# Sheet1.net
KiCad netlist of a schematic drawn in Altium Designer
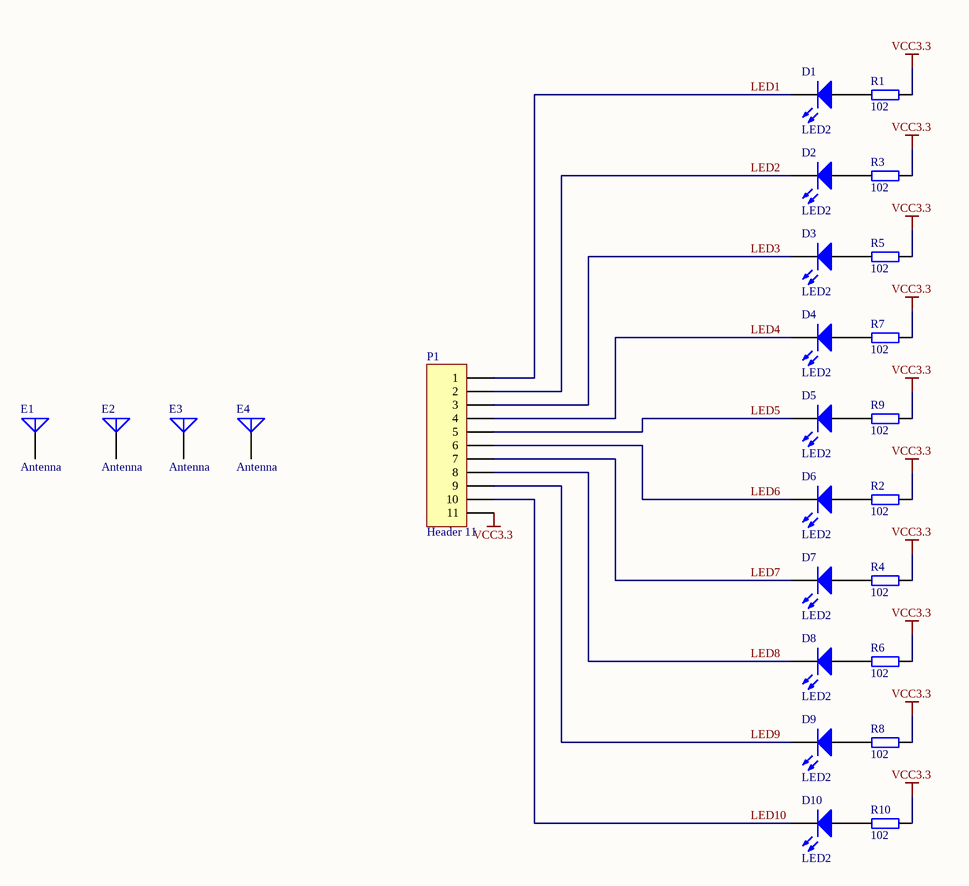
[diagram p0: Sheet1.SchDoc]

(export (version "E")
  (design (tool "Eeschema 10.0.6"))
  (components
    (comp (ref "D1")
      (value "LED2")
      (footprint "LED1")
      (description "Typical RED, GREEN, YELLOW, AMBER GaAs LED")
      (fields (field (name "PUBLISHER") "Altium Limited"))
      (libsource (lib "Miscellaneous Devices") (part "LED2"))
    )
    (comp (ref "D2")
      (value "LED2")
      (footprint "LED1")
      (description "Typical RED, GREEN, YELLOW, AMBER GaAs LED")
      (fields (field (name "PUBLISHER") "Altium Limited"))
      (libsource (lib "Miscellaneous Devices") (part "LED2"))
    )
    (comp (ref "D3")
      (value "LED2")
      (footprint "LED1")
      (description "Typical RED, GREEN, YELLOW, AMBER GaAs LED")
      (fields (field (name "PUBLISHER") "Altium Limited"))
      (libsource (lib "Miscellaneous Devices") (part "LED2"))
    )
    (comp (ref "D4")
      (value "LED2")
      (footprint "LED1")
      (description "Typical RED, GREEN, YELLOW, AMBER GaAs LED")
      (fields (field (name "PUBLISHER") "Altium Limited"))
      (libsource (lib "Miscellaneous Devices") (part "LED2"))
    )
    (comp (ref "D5")
      (value "LED2")
      (footprint "LED1")
      (description "Typical RED, GREEN, YELLOW, AMBER GaAs LED")
      (fields (field (name "PUBLISHER") "Altium Limited"))
      (libsource (lib "Miscellaneous Devices") (part "LED2"))
    )
    (comp (ref "D6")
      (value "LED2")
      (footprint "LED1")
      (description "Typical RED, GREEN, YELLOW, AMBER GaAs LED")
      (fields (field (name "PUBLISHER") "Altium Limited"))
      (libsource (lib "Miscellaneous Devices") (part "LED2"))
    )
    (comp (ref "D7")
      (value "LED2")
      (footprint "LED1")
      (description "Typical RED, GREEN, YELLOW, AMBER GaAs LED")
      (fields (field (name "PUBLISHER") "Altium Limited"))
      (libsource (lib "Miscellaneous Devices") (part "LED2"))
    )
    (comp (ref "D8")
      (value "LED2")
      (footprint "LED1")
      (description "Typical RED, GREEN, YELLOW, AMBER GaAs LED")
      (fields (field (name "PUBLISHER") "Altium Limited"))
      (libsource (lib "Miscellaneous Devices") (part "LED2"))
    )
    (comp (ref "D9")
      (value "LED2")
      (footprint "LED1")
      (description "Typical RED, GREEN, YELLOW, AMBER GaAs LED")
      (fields (field (name "PUBLISHER") "Altium Limited"))
      (libsource (lib "Miscellaneous Devices") (part "LED2"))
    )
    (comp (ref "D10")
      (value "LED2")
      (footprint "LED1")
      (description "Typical RED, GREEN, YELLOW, AMBER GaAs LED")
      (fields (field (name "PUBLISHER") "Altium Limited"))
      (libsource (lib "Miscellaneous Devices") (part "LED2"))
    )
    (comp (ref "E1")
      (value "Antenna")
      (footprint "定位孔 Φ3.2")
      (description "Generic Antenna")
      (fields (field (name "PUBLISHER") "Altium Limited"))
      (libsource (lib "Miscellaneous Devices") (part "Antenna"))
    )
    (comp (ref "E2")
      (value "Antenna")
      (footprint "定位孔 Φ3.2")
      (description "Generic Antenna")
      (fields (field (name "PUBLISHER") "Altium Limited"))
      (libsource (lib "Miscellaneous Devices") (part "Antenna"))
    )
    (comp (ref "E3")
      (value "Antenna")
      (footprint "定位孔 Φ3.2")
      (description "Generic Antenna")
      (fields (field (name "PUBLISHER") "Altium Limited"))
      (libsource (lib "Miscellaneous Devices") (part "Antenna"))
    )
    (comp (ref "E4")
      (value "Antenna")
      (footprint "定位孔 Φ3.2")
      (description "Generic Antenna")
      (fields (field (name "PUBLISHER") "Altium Limited"))
      (libsource (lib "Miscellaneous Devices") (part "Antenna"))
    )
    (comp (ref "P1")
      (value "Header 11")
      (footprint "XH11")
      (description "Header, 11-Pin")
      (fields (field (name "PUBLISHER") "Altium Limited"))
      (libsource (lib "Miscellaneous Connectors") (part "Header 11"))
    )
    (comp (ref "R1")
      (value "102")
      (footprint "0603_R")
      (libsource (lib "Explorer STM32F407封装库") (part "R_2"))
    )
    (comp (ref "R2")
      (value "102")
      (footprint "0603_R")
      (libsource (lib "Explorer STM32F407封装库") (part "R_2"))
    )
    (comp (ref "R3")
      (value "102")
      (footprint "0603_R")
      (libsource (lib "Explorer STM32F407封装库") (part "R_2"))
    )
    (comp (ref "R4")
      (value "102")
      (footprint "0603_R")
      (libsource (lib "Explorer STM32F407封装库") (part "R_2"))
    )
    (comp (ref "R5")
      (value "102")
      (footprint "0603_R")
      (libsource (lib "Explorer STM32F407封装库") (part "R_2"))
    )
    (comp (ref "R6")
      (value "102")
      (footprint "0603_R")
      (libsource (lib "Explorer STM32F407封装库") (part "R_2"))
    )
    (comp (ref "R7")
      (value "102")
      (footprint "0603_R")
      (libsource (lib "Explorer STM32F407封装库") (part "R_2"))
    )
    (comp (ref "R8")
      (value "102")
      (footprint "0603_R")
      (libsource (lib "Explorer STM32F407封装库") (part "R_2"))
    )
    (comp (ref "R9")
      (value "102")
      (footprint "0603_R")
      (libsource (lib "Explorer STM32F407封装库") (part "R_2"))
    )
    (comp (ref "R10")
      (value "102")
      (footprint "0603_R")
      (libsource (lib "Explorer STM32F407封装库") (part "R_2"))
    )
  )
  (nets
    (net (code "1") (name "/LED1") (class "Default")
      (node (ref "D1") (pin "2") (pinfunction "K_2") (pintype "passive"))
      (node (ref "P1") (pin "1") (pinfunction "1_1") (pintype "passive"))
    )
    (net (code "2") (name "/LED2") (class "Default")
      (node (ref "D2") (pin "2") (pinfunction "K_2") (pintype "passive"))
      (node (ref "P1") (pin "2") (pinfunction "2_2") (pintype "passive"))
    )
    (net (code "3") (name "/LED3") (class "Default")
      (node (ref "D3") (pin "2") (pinfunction "K_2") (pintype "passive"))
      (node (ref "P1") (pin "3") (pinfunction "3_3") (pintype "passive"))
    )
    (net (code "4") (name "/LED4") (class "Default")
      (node (ref "D4") (pin "2") (pinfunction "K_2") (pintype "passive"))
      (node (ref "P1") (pin "4") (pinfunction "4_4") (pintype "passive"))
    )
    (net (code "5") (name "/LED5") (class "Default")
      (node (ref "D5") (pin "2") (pinfunction "K_2") (pintype "passive"))
      (node (ref "P1") (pin "5") (pinfunction "5_5") (pintype "passive"))
    )
    (net (code "6") (name "/LED6") (class "Default")
      (node (ref "D6") (pin "2") (pinfunction "K_2") (pintype "passive"))
      (node (ref "P1") (pin "6") (pinfunction "6_6") (pintype "passive"))
    )
    (net (code "7") (name "/LED7") (class "Default")
      (node (ref "D7") (pin "2") (pinfunction "K_2") (pintype "passive"))
      (node (ref "P1") (pin "7") (pinfunction "7_7") (pintype "passive"))
    )
    (net (code "8") (name "/LED8") (class "Default")
      (node (ref "D8") (pin "2") (pinfunction "K_2") (pintype "passive"))
      (node (ref "P1") (pin "8") (pinfunction "8_8") (pintype "passive"))
    )
    (net (code "9") (name "/LED9") (class "Default")
      (node (ref "D9") (pin "2") (pinfunction "K_2") (pintype "passive"))
      (node (ref "P1") (pin "9") (pinfunction "9_9") (pintype "passive"))
    )
    (net (code "10") (name "/LED10") (class "Default")
      (node (ref "D10") (pin "2") (pinfunction "K_2") (pintype "passive"))
      (node (ref "P1") (pin "10") (pinfunction "10_10") (pintype "passive"))
    )
    (net (code "11") (name "Net-(D1-A)") (class "Default")
      (node (ref "D1") (pin "1") (pinfunction "A_1") (pintype "passive"))
      (node (ref "R1") (pin "1") (pintype "passive"))
    )
    (net (code "12") (name "Net-(D2-A)") (class "Default")
      (node (ref "D2") (pin "1") (pinfunction "A_1") (pintype "passive"))
      (node (ref "R3") (pin "1") (pintype "passive"))
    )
    (net (code "13") (name "Net-(D3-A)") (class "Default")
      (node (ref "D3") (pin "1") (pinfunction "A_1") (pintype "passive"))
      (node (ref "R5") (pin "1") (pintype "passive"))
    )
    (net (code "14") (name "Net-(D4-A)") (class "Default")
      (node (ref "D4") (pin "1") (pinfunction "A_1") (pintype "passive"))
      (node (ref "R7") (pin "1") (pintype "passive"))
    )
    (net (code "15") (name "Net-(D5-A)") (class "Default")
      (node (ref "D5") (pin "1") (pinfunction "A_1") (pintype "passive"))
      (node (ref "R9") (pin "1") (pintype "passive"))
    )
    (net (code "16") (name "Net-(D6-A)") (class "Default")
      (node (ref "D6") (pin "1") (pinfunction "A_1") (pintype "passive"))
      (node (ref "R2") (pin "1") (pintype "passive"))
    )
    (net (code "17") (name "Net-(D7-A)") (class "Default")
      (node (ref "D7") (pin "1") (pinfunction "A_1") (pintype "passive"))
      (node (ref "R4") (pin "1") (pintype "passive"))
    )
    (net (code "18") (name "Net-(D8-A)") (class "Default")
      (node (ref "D8") (pin "1") (pinfunction "A_1") (pintype "passive"))
      (node (ref "R6") (pin "1") (pintype "passive"))
    )
    (net (code "19") (name "Net-(D9-A)") (class "Default")
      (node (ref "D9") (pin "1") (pinfunction "A_1") (pintype "passive"))
      (node (ref "R8") (pin "1") (pintype "passive"))
    )
    (net (code "20") (name "Net-(D10-A)") (class "Default")
      (node (ref "D10") (pin "1") (pinfunction "A_1") (pintype "passive"))
      (node (ref "R10") (pin "1") (pintype "passive"))
    )
    (net (code "21") (name "VCC3.3") (class "Default")
      (node (ref "P1") (pin "11") (pinfunction "11_11") (pintype "passive"))
      (node (ref "R1") (pin "2") (pintype "passive"))
      (node (ref "R10") (pin "2") (pintype "passive"))
      (node (ref "R2") (pin "2") (pintype "passive"))
      (node (ref "R3") (pin "2") (pintype "passive"))
      (node (ref "R4") (pin "2") (pintype "passive"))
      (node (ref "R5") (pin "2") (pintype "passive"))
      (node (ref "R6") (pin "2") (pintype "passive"))
      (node (ref "R7") (pin "2") (pintype "passive"))
      (node (ref "R8") (pin "2") (pintype "passive"))
      (node (ref "R9") (pin "2") (pintype "passive"))
    )
    (net (code "22") (name "unconnected-(E1-A-Pad1)") (class "Default")
      (node (ref "E1") (pin "1") (pinfunction "A_1") (pintype "passive"))
    )
    (net (code "23") (name "unconnected-(E2-A-Pad1)") (class "Default")
      (node (ref "E2") (pin "1") (pinfunction "A_1") (pintype "passive"))
    )
    (net (code "24") (name "unconnected-(E3-A-Pad1)") (class "Default")
      (node (ref "E3") (pin "1") (pinfunction "A_1") (pintype "passive"))
    )
    (net (code "25") (name "unconnected-(E4-A-Pad1)") (class "Default")
      (node (ref "E4") (pin "1") (pinfunction "A_1") (pintype "passive"))
    )
  )
)
